# Fonte.net
KiCad netlist of a schematic drawn in Altium Designer
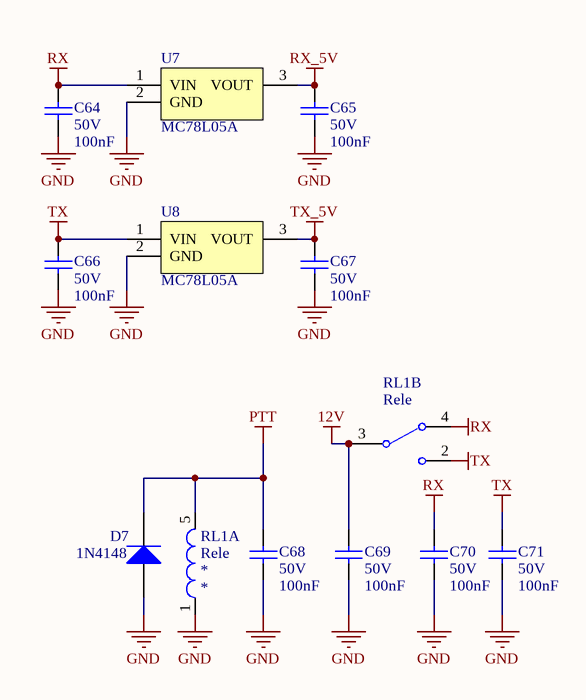
[diagram p0: Fonte.SchDoc]

(export (version "E")
  (design (tool "Eeschema 10.0.6"))
  (components
    (comp (ref "C64")
      (value "100nF")
      (footprint "CC0603")
      (description "Capacitor (Semiconductor SIM Model)")
      (fields (field (name "TENSÃO") "50V") (field (name "Comment") "Capacitor Cerâmico"))
      (libsource (lib "NavarroCAP") (part "Cap 100nF 50V 0603 X7R"))
    )
    (comp (ref "C65")
      (value "100nF")
      (footprint "CC0603")
      (description "Capacitor (Semiconductor SIM Model)")
      (fields (field (name "TENSÃO") "50V") (field (name "Comment") "Capacitor Cerâmico"))
      (libsource (lib "NavarroCAP") (part "Cap 100nF 50V 0603 X7R"))
    )
    (comp (ref "C66")
      (value "100nF")
      (footprint "CC0603")
      (description "Capacitor (Semiconductor SIM Model)")
      (fields (field (name "TENSÃO") "50V") (field (name "Comment") "Capacitor Cerâmico"))
      (libsource (lib "NavarroCAP") (part "Cap 100nF 50V 0603 X7R"))
    )
    (comp (ref "C67")
      (value "100nF")
      (footprint "CC0603")
      (description "Capacitor (Semiconductor SIM Model)")
      (fields (field (name "TENSÃO") "50V") (field (name "Comment") "Capacitor Cerâmico"))
      (libsource (lib "NavarroCAP") (part "Cap 100nF 50V 0603 X7R"))
    )
    (comp (ref "C68")
      (value "100nF")
      (footprint "CC0603")
      (description "Capacitor (Semiconductor SIM Model)")
      (fields (field (name "TENSÃO") "50V") (field (name "Comment") "Capacitor Cerâmico"))
      (libsource (lib "NavarroCAP") (part "Cap 100nF 50V 0603 X7R"))
    )
    (comp (ref "C69")
      (value "100nF")
      (footprint "CC0603")
      (description "Capacitor (Semiconductor SIM Model)")
      (fields (field (name "TENSÃO") "50V") (field (name "Comment") "Capacitor Cerâmico"))
      (libsource (lib "NavarroCAP") (part "Cap 100nF 50V 0603 X7R"))
    )
    (comp (ref "C70")
      (value "100nF")
      (footprint "CC0603")
      (description "Capacitor (Semiconductor SIM Model)")
      (fields (field (name "TENSÃO") "50V") (field (name "Comment") "Capacitor Cerâmico"))
      (libsource (lib "NavarroCAP") (part "Cap 100nF 50V 0603 X7R"))
    )
    (comp (ref "C71")
      (value "100nF")
      (footprint "CC0603")
      (description "Capacitor (Semiconductor SIM Model)")
      (fields (field (name "TENSÃO") "50V") (field (name "Comment") "Capacitor Cerâmico"))
      (libsource (lib "NavarroCAP") (part "Cap 100nF 50V 0603 X7R"))
    )
    (comp (ref "D7")
      (value "1N4148")
      (footprint "SOD-323 Diodo-K2")
      (description "Small Signal Diodes")
      (libsource (lib "NavarroSEMI") (part "DP 75V 150mA SOD-323"))
    )
    (comp (ref "RL1")
      (value "Rele")
      (footprint "Rele SPDT")
      (description "Rele de uma chave e dois contatos")
      (fields (field (name "CORRENTE") "*") (field (name "TENSÃO") "*"))
      (libsource (lib "Navarro") (part "Rele SPDT"))
    )
    (comp (ref "U7")
      (value "MC78L05A")
      (footprint "SOT-89-3N")
      (description "Regulador Linear 5V")
      (libsource (lib "Navarro") (part "MC78L05"))
    )
    (comp (ref "U8")
      (value "MC78L05A")
      (footprint "SOT-89-3N")
      (description "Regulador Linear 5V")
      (libsource (lib "Navarro") (part "MC78L05"))
    )
  )
  (nets
    (net (code "1") (name "12V") (class "Default")
      (node (ref "C69") (pin "2") (pinfunction "2_2") (pintype "passive"))
      (node (ref "RL1") (pin "3") (pinfunction "C_3") (pintype "passive"))
    )
    (net (code "2") (name "GND") (class "Default")
      (node (ref "C64") (pin "1") (pinfunction "1_1") (pintype "passive"))
      (node (ref "C65") (pin "1") (pinfunction "1_1") (pintype "passive"))
      (node (ref "C66") (pin "1") (pinfunction "1_1") (pintype "passive"))
      (node (ref "C67") (pin "1") (pinfunction "1_1") (pintype "passive"))
      (node (ref "C68") (pin "1") (pinfunction "1_1") (pintype "passive"))
      (node (ref "C69") (pin "1") (pinfunction "1_1") (pintype "passive"))
      (node (ref "C70") (pin "1") (pinfunction "1_1") (pintype "passive"))
      (node (ref "C71") (pin "1") (pinfunction "1_1") (pintype "passive"))
      (node (ref "D7") (pin "1") (pinfunction "A_1") (pintype "passive"))
      (node (ref "RL1") (pin "1") (pinfunction "L1_1") (pintype "passive"))
      (node (ref "U7") (pin "2") (pinfunction "GND_2") (pintype "power_in"))
      (node (ref "U8") (pin "2") (pinfunction "GND_2") (pintype "power_in"))
    )
    (net (code "3") (name "PTT") (class "Default")
      (node (ref "C68") (pin "2") (pinfunction "2_2") (pintype "passive"))
      (node (ref "D7") (pin "2") (pinfunction "K_2") (pintype "passive"))
      (node (ref "RL1") (pin "5") (pinfunction "L2_5") (pintype "passive"))
    )
    (net (code "4") (name "RX") (class "Default")
      (node (ref "C64") (pin "2") (pinfunction "2_2") (pintype "passive"))
      (node (ref "C70") (pin "2") (pinfunction "2_2") (pintype "passive"))
      (node (ref "RL1") (pin "4") (pinfunction "NF_4") (pintype "passive"))
      (node (ref "U7") (pin "1") (pinfunction "VIN_1") (pintype "power_in"))
    )
    (net (code "5") (name "RX_5V") (class "Default")
      (node (ref "C65") (pin "2") (pinfunction "2_2") (pintype "passive"))
      (node (ref "U7") (pin "3") (pinfunction "VOUT_3") (pintype "power_in"))
    )
    (net (code "6") (name "TX") (class "Default")
      (node (ref "C66") (pin "2") (pinfunction "2_2") (pintype "passive"))
      (node (ref "C71") (pin "2") (pinfunction "2_2") (pintype "passive"))
      (node (ref "RL1") (pin "2") (pinfunction "NA_2") (pintype "passive"))
      (node (ref "U8") (pin "1") (pinfunction "VIN_1") (pintype "power_in"))
    )
    (net (code "7") (name "TX_5V") (class "Default")
      (node (ref "C67") (pin "2") (pinfunction "2_2") (pintype "passive"))
      (node (ref "U8") (pin "3") (pinfunction "VOUT_3") (pintype "power_in"))
    )
  )
)
